# RS232_Level_Shifter.net
KiCad netlist of a schematic drawn in Altium Designer
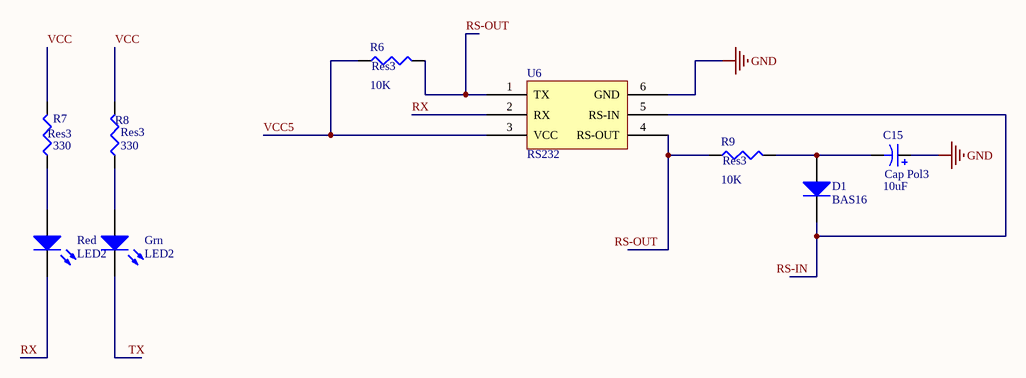
[diagram p0: RS232_Level_Shifter.SchDoc]

(export (version "E")
  (design (tool "Eeschema 10.0.6"))
  (components
    (comp (ref "C15")
      (value "Cap Pol3")
      (footprint "C0805")
      (description "Polarized Capacitor (Surface Mount)")
      (fields (field (name "ALTIUM_VALUE") "10uF") (field (name "PUBLISHER") "Altium Limited"))
      (libsource (lib "Miscellaneous Devices") (part "Cap Pol3"))
    )
    (comp (ref "D1")
      (value "BAS16")
      (footprint "SMC")
      (description "Default Diode")
      (fields (field (name "PUBLISHER") "Altium Limited"))
      (libsource (lib "Miscellaneous Devices") (part "Diode"))
    )
    (comp (ref "Grn")
      (value "LED2")
      (footprint "3.2X1.6X1.1")
      (description "Typical RED, GREEN, YELLOW, AMBER GaAs LED")
      (fields (field (name "PUBLISHER") "Altium Limited"))
      (libsource (lib "Miscellaneous Devices") (part "LED2"))
    )
    (comp (ref "R6")
      (value "Res3")
      (footprint "J1-0603")
      (description "Resistor")
      (fields (field (name "ALTIUM_VALUE") "10K") (field (name "PUBLISHER") "Altium Limited"))
      (libsource (lib "Miscellaneous Devices") (part "Res3"))
    )
    (comp (ref "R7")
      (value "Res3")
      (footprint "J1-0603")
      (description "Resistor")
      (fields (field (name "ALTIUM_VALUE") "330") (field (name "PUBLISHER") "Altium Limited"))
      (libsource (lib "Miscellaneous Devices") (part "Res3"))
    )
    (comp (ref "R8")
      (value "Res3")
      (footprint "J1-0603")
      (description "Resistor")
      (fields (field (name "ALTIUM_VALUE") "330") (field (name "PUBLISHER") "Altium Limited"))
      (libsource (lib "Miscellaneous Devices") (part "Res3"))
    )
    (comp (ref "R9")
      (value "Res3")
      (footprint "J1-0603")
      (description "Resistor")
      (fields (field (name "ALTIUM_VALUE") "10K") (field (name "PUBLISHER") "Altium Limited"))
      (libsource (lib "Miscellaneous Devices") (part "Res3"))
    )
    (comp (ref "Red")
      (value "LED2")
      (footprint "3.2X1.6X1.1")
      (description "Typical RED, GREEN, YELLOW, AMBER GaAs LED")
      (fields (field (name "PUBLISHER") "Altium Limited"))
      (libsource (lib "Miscellaneous Devices") (part "LED2"))
    )
    (comp (ref "U6")
      (value "RS232")
      (footprint "rs232")
      (libsource (lib "RS232_Level_Shifter") (part "RS232"))
    )
  )
  (nets
    (net (code "2") (name "/RS-OUT") (class "Default")
      (node (ref "R6") (pin "2") (pinfunction "2_2") (pintype "passive"))
      (node (ref "U6") (pin "1") (pinfunction "TX_1") (pintype "passive"))
    )
    (net (code "3") (name "/RX") (class "Default")
      (node (ref "Red") (pin "2") (pinfunction "K_2") (pintype "passive"))
      (node (ref "U6") (pin "2") (pinfunction "RX_2") (pintype "passive"))
    )
    (net (code "4") (name "/TX") (class "Default")
      (node (ref "Grn") (pin "2") (pinfunction "K_2") (pintype "passive"))
    )
    (net (code "5") (name "/VCC") (class "Default")
      (node (ref "R7") (pin "2") (pinfunction "2_2") (pintype "passive"))
      (node (ref "R8") (pin "2") (pinfunction "2_2") (pintype "passive"))
    )
    (net (code "6") (name "/VCC5") (class "Default")
      (node (ref "R6") (pin "1") (pinfunction "1_1") (pintype "passive"))
      (node (ref "U6") (pin "3") (pinfunction "VCC_3") (pintype "passive"))
    )
    (net (code "7") (name "GND") (class "Default")
      (node (ref "C15") (pin "1") (pinfunction "1_1") (pintype "passive"))
      (node (ref "U6") (pin "6") (pinfunction "GND_6") (pintype "passive"))
    )
    (net (code "8") (name "Net-(D1-A)") (class "Default")
      (node (ref "C15") (pin "2") (pinfunction "2_2") (pintype "passive"))
      (node (ref "D1") (pin "1") (pinfunction "A_1") (pintype "passive"))
      (node (ref "R9") (pin "2") (pinfunction "2_2") (pintype "passive"))
    )
    (net (code "9") (name "Net-(D1-K)") (class "Default")
      (node (ref "D1") (pin "2") (pinfunction "K_2") (pintype "passive"))
      (node (ref "U6") (pin "5") (pinfunction "RS-IN_5") (pintype "passive"))
    )
    (net (code "10") (name "Net-(Grn-A)") (class "Default")
      (node (ref "Grn") (pin "1") (pinfunction "A_1") (pintype "passive"))
      (node (ref "R8") (pin "1") (pinfunction "1_1") (pintype "passive"))
    )
    (net (code "11") (name "Net-(Red-A)") (class "Default")
      (node (ref "R7") (pin "1") (pinfunction "1_1") (pintype "passive"))
      (node (ref "Red") (pin "1") (pinfunction "A_1") (pintype "passive"))
    )
    (net (code "12") (name "Net-(U6-RS-OUT)") (class "Default")
      (node (ref "R9") (pin "1") (pinfunction "1_1") (pintype "passive"))
      (node (ref "U6") (pin "4") (pinfunction "RS-OUT_4") (pintype "passive"))
    )
  )
)
